# 7seg4digits.net
KiCad netlist of a schematic drawn in EAGLE
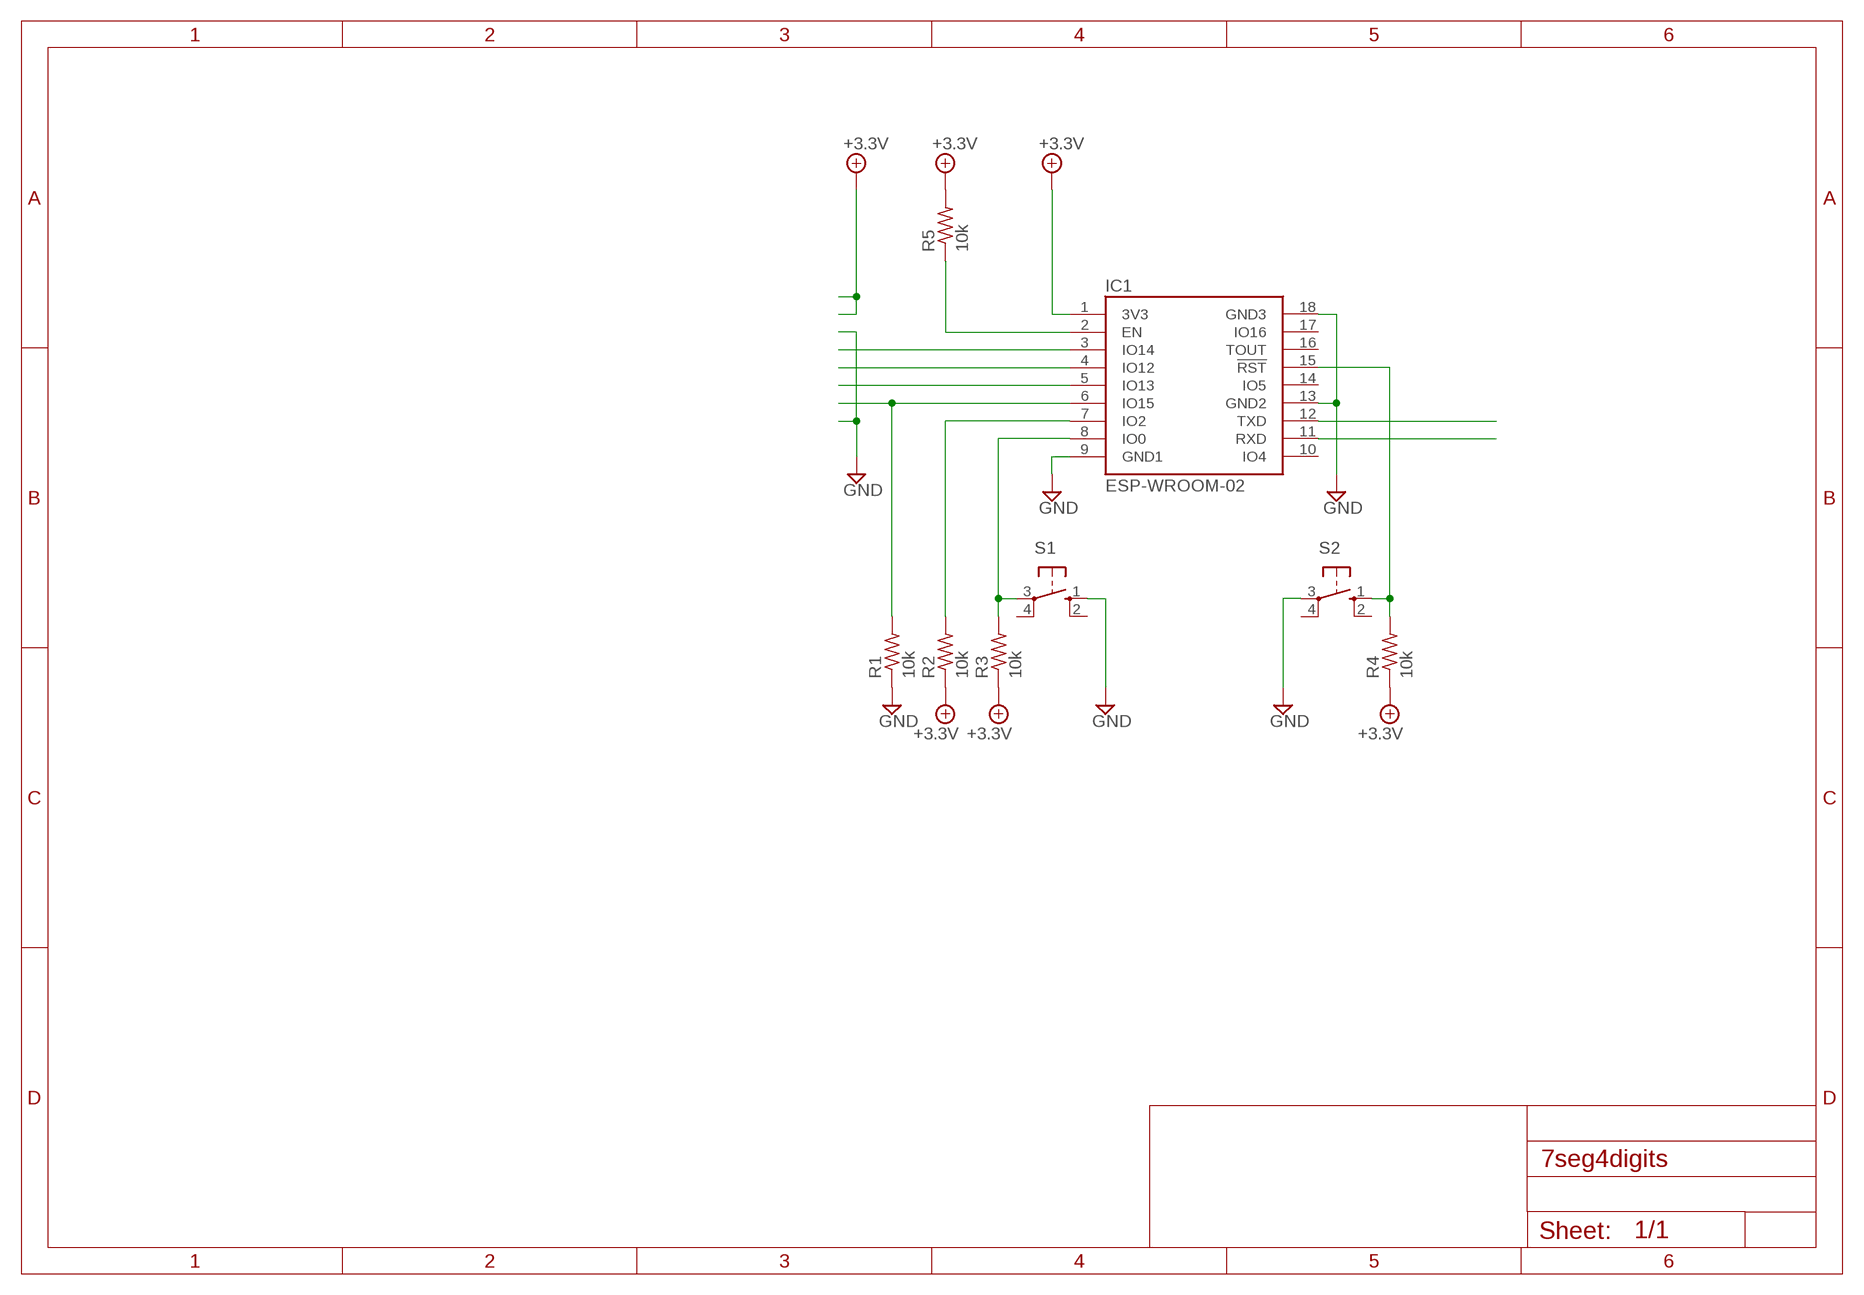
[diagram p0: schematic, sheet 1]

(export (version "E")
  (design (tool "Eeschema 10.0.6"))
  (components
    (comp (ref "IC1")
      (value "ESP-WROOM-02")
      (footprint "eagle-import:WROOM-02")
      (libsource (lib "eagle-import") (part "ESP-WROOM-02"))
    )
    (comp (ref "R1")
      (value "10k")
      (footprint "eagle-import:0309_12")
      (libsource (lib "eagle-import") (part "R"))
    )
    (comp (ref "R2")
      (value "10k")
      (footprint "eagle-import:0309_12")
      (libsource (lib "eagle-import") (part "R"))
    )
    (comp (ref "R3")
      (value "10k")
      (footprint "eagle-import:0309_12")
      (libsource (lib "eagle-import") (part "R"))
    )
    (comp (ref "R4")
      (value "10k")
      (footprint "eagle-import:0309_12")
      (libsource (lib "eagle-import") (part "R"))
    )
    (comp (ref "R5")
      (value "10k")
      (footprint "eagle-import:0309_12")
      (libsource (lib "eagle-import") (part "R"))
    )
    (comp (ref "S1")
      (value "10-XX(タクトスイッチ)")
      (footprint "eagle-import:B3F-10XX")
      (fields (field (name "MPN") "B3F-1000"))
      (libsource (lib "eagle-import") (part "10-XX(タクトスイッチ)"))
    )
    (comp (ref "S2")
      (value "10-XX(タクトスイッチ)")
      (footprint "eagle-import:B3F-10XX")
      (fields (field (name "MPN") "B3F-1000"))
      (libsource (lib "eagle-import") (part "10-XX(タクトスイッチ)"))
    )
  )
  (nets
    (net (code "1") (name "+3.3V") (class "Default")
      (node (ref "IC1") (pin "1") (pinfunction "3V3_1") (pintype "power_in"))
      (node (ref "R2") (pin "1") (pinfunction "1_1") (pintype "passive"))
      (node (ref "R3") (pin "1") (pinfunction "1_1") (pintype "passive"))
      (node (ref "R4") (pin "1") (pinfunction "1_1") (pintype "passive"))
      (node (ref "R5") (pin "2") (pinfunction "2_2") (pintype "passive"))
    )
    (net (code "2") (name "GND") (class "Default")
      (node (ref "IC1") (pin "13") (pinfunction "GND2_13") (pintype "power_in"))
      (node (ref "IC1") (pin "18") (pinfunction "GND3_18") (pintype "power_in"))
      (node (ref "IC1") (pin "9") (pinfunction "GND1_9") (pintype "power_in"))
      (node (ref "R1") (pin "1") (pinfunction "1_1") (pintype "passive"))
      (node (ref "S1") (pin "1") (pinfunction "S_1") (pintype "passive"))
      (node (ref "S2") (pin "3") (pinfunction "P_3") (pintype "passive"))
    )
    (net (code "3") (name "Net-(IC1-EN)") (class "Default")
      (node (ref "IC1") (pin "2") (pinfunction "EN_2") (pintype "input"))
      (node (ref "R5") (pin "1") (pinfunction "1_1") (pintype "passive"))
    )
    (net (code "4") (name "Net-(IC1-IO0)") (class "Default")
      (node (ref "IC1") (pin "8") (pinfunction "IO0_8") (pintype "bidirectional"))
      (node (ref "R3") (pin "2") (pinfunction "2_2") (pintype "passive"))
      (node (ref "S1") (pin "3") (pinfunction "P_3") (pintype "passive"))
    )
    (net (code "5") (name "Net-(IC1-IO2)") (class "Default")
      (node (ref "IC1") (pin "7") (pinfunction "IO2_7") (pintype "bidirectional"))
      (node (ref "R2") (pin "2") (pinfunction "2_2") (pintype "passive"))
    )
    (net (code "6") (name "Net-(IC1-IO15)") (class "Default")
      (node (ref "IC1") (pin "6") (pinfunction "IO15_6") (pintype "bidirectional"))
      (node (ref "R1") (pin "2") (pinfunction "2_2") (pintype "passive"))
    )
    (net (code "7") (name "Net-(IC1-~{RST})") (class "Default")
      (node (ref "IC1") (pin "15") (pinfunction "~{RST}_15") (pintype "input"))
      (node (ref "R4") (pin "2") (pinfunction "2_2") (pintype "passive"))
      (node (ref "S2") (pin "1") (pinfunction "S_1") (pintype "passive"))
    )
    (net (code "8") (name "unconnected-(IC1-IO4-Pad10)") (class "Default")
      (node (ref "IC1") (pin "10") (pinfunction "IO4_10") (pintype "bidirectional"))
    )
    (net (code "9") (name "unconnected-(IC1-IO5-Pad14)") (class "Default")
      (node (ref "IC1") (pin "14") (pinfunction "IO5_14") (pintype "bidirectional"))
    )
    (net (code "10") (name "unconnected-(IC1-IO12-Pad4)") (class "Default")
      (node (ref "IC1") (pin "4") (pinfunction "IO12_4") (pintype "bidirectional"))
    )
    (net (code "11") (name "unconnected-(IC1-IO13-Pad5)") (class "Default")
      (node (ref "IC1") (pin "5") (pinfunction "IO13_5") (pintype "bidirectional"))
    )
    (net (code "12") (name "unconnected-(IC1-IO14-Pad3)") (class "Default")
      (node (ref "IC1") (pin "3") (pinfunction "IO14_3") (pintype "bidirectional"))
    )
    (net (code "13") (name "unconnected-(IC1-IO16-Pad17)") (class "Default")
      (node (ref "IC1") (pin "17") (pinfunction "IO16_17") (pintype "bidirectional"))
    )
    (net (code "14") (name "unconnected-(IC1-RXD-Pad11)") (class "Default")
      (node (ref "IC1") (pin "11") (pinfunction "RXD_11") (pintype "bidirectional"))
    )
    (net (code "15") (name "unconnected-(IC1-TOUT-Pad16)") (class "Default")
      (node (ref "IC1") (pin "16") (pinfunction "TOUT_16") (pintype "bidirectional"))
    )
    (net (code "16") (name "unconnected-(IC1-TXD-Pad12)") (class "Default")
      (node (ref "IC1") (pin "12") (pinfunction "TXD_12") (pintype "bidirectional"))
    )
    (net (code "17") (name "unconnected-(S1-P1-Pad4)") (class "Default")
      (node (ref "S1") (pin "4") (pinfunction "P1_4") (pintype "passive"))
    )
    (net (code "18") (name "unconnected-(S1-S1-Pad2)") (class "Default")
      (node (ref "S1") (pin "2") (pinfunction "S1_2") (pintype "passive"))
    )
    (net (code "19") (name "unconnected-(S2-P1-Pad4)") (class "Default")
      (node (ref "S2") (pin "4") (pinfunction "P1_4") (pintype "passive"))
    )
    (net (code "20") (name "unconnected-(S2-S1-Pad2)") (class "Default")
      (node (ref "S2") (pin "2") (pinfunction "S1_2") (pintype "passive"))
    )
  )
)
